# cont_board.net
KiCad netlist of a schematic drawn in Altium Designer
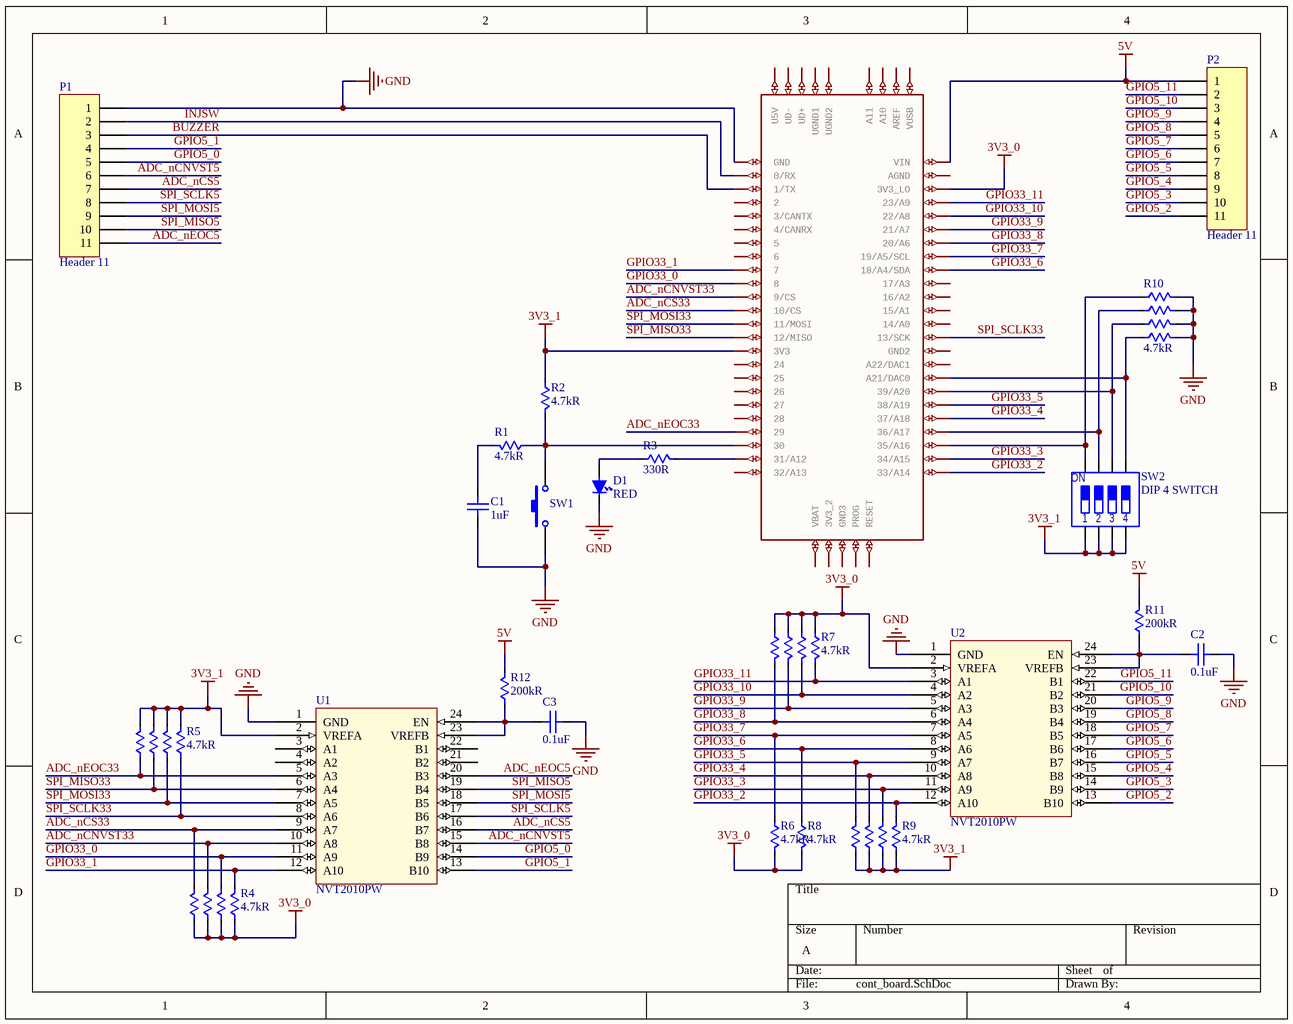
[diagram p0: cont_board.SchDoc]

(export (version "E")
  (design (tool "Eeschema 10.0.6"))
  (components
    (comp (ref "1")
      (value "TEENSY_3.5/3.6")
      (footprint "TEENSY_3.5/3.6")
      (libsource (lib "Schlib1") (part "TEENSY_3.5/3.6"))
    )
    (comp (ref "C1")
      (value "1uF")
      (footprint "CAP_0805")
      (description "Cap Ceramic 1uF 16V Y5V -20% to 80% Pad SMD 0805 85C T/R")
      (fields
        (field (name "MANUFACTURER") "KEMET")
        (field (name "MANUFACTURER PART NUMBER") "C0805C105Z4VACTU")
      )
      (libsource (lib "Schlib1") (part "C0805C105Z4VACTU"))
    )
    (comp (ref "C2")
      (value "0.1uF")
      (footprint "CAP_0805")
      (description "CAP CER 0.1UF 25V X7R 0805")
      (fields (field (name "MANUFACTURER") "KEMET") (field (name "TOLERANCE") "20%"))
      (libsource (lib "Schlib1") (part "C0805C104M3RACTU"))
    )
    (comp (ref "C3")
      (value "0.1uF")
      (footprint "CAP_0805")
      (description "CAP CER 0.1UF 25V X7R 0805")
      (fields (field (name "MANUFACTURER") "KEMET") (field (name "TOLERANCE") "20%"))
      (libsource (lib "Schlib1") (part "C0805C104M3RACTU"))
    )
    (comp (ref "D1")
      (value "RED")
      (footprint "150080SS75000")
      (description "WURTH ELEKTRONIK   150080SS75000   LED, 0805, SUP RED, 60MCD, 630NM")
      (fields
        (field (name "MANUFACTURER") "Wurth Electronics")
        (field (name "MANUFACTURER PART NUMBER") "150080SS75000")
      )
      (libsource (lib "Schlib1") (part "150080SS75000"))
    )
    (comp (ref "P1")
      (value "Header 11")
      (footprint "HDR1X11")
      (description "Header, 11-Pin")
      (fields (field (name "PUBLISHER") "Altium Limited"))
      (libsource (lib "Miscellaneous Connectors") (part "Header 11"))
    )
    (comp (ref "P2")
      (value "Header 11")
      (footprint "HDR1X11")
      (description "Header, 11-Pin")
      (fields (field (name "PUBLISHER") "Altium Limited"))
      (libsource (lib "") (part "Header 11_1"))
    )
    (comp (ref "R1")
      (value "4.7kR")
      (footprint "RES_0805_PANASONIC")
      (description "Res Thin Film 0805 4.7K Ohm 0.5% 0.125W(1/8W) ±25ppm/C Molded SMD Automotive Punched T/R")
      (fields
        (field (name "MANUFACTURER") "Panasonic")
        (field (name "MANUFACTURER PART NUMBER") "ERA-6AED472V")
      )
      (libsource (lib "Schlib1") (part "ERA-6AED472V"))
    )
    (comp (ref "R2")
      (value "4.7kR")
      (footprint "RES_0805_PANASONIC")
      (description "Res Thin Film 0805 4.7K Ohm 0.5% 0.125W(1/8W) ±25ppm/C Molded SMD Automotive Punched T/R")
      (fields
        (field (name "MANUFACTURER") "Panasonic")
        (field (name "MANUFACTURER PART NUMBER") "ERA-6AED472V")
      )
      (libsource (lib "Schlib1") (part "ERA-6AED472V"))
    )
    (comp (ref "R3")
      (value "330R")
      (footprint "RES_0805_PANASONIC")
      (description "Res Thin Film 0805 330 Ohm 0.5% 0.125W(1/8W) ±25ppm/C Molded SMD Automotive Punched T/R")
      (fields
        (field (name "MANUFACTURER") "Panasonic")
        (field (name "MANUFACTURER PART NUMBER") "ERA-6AED331V")
      )
      (libsource (lib "Schlib1") (part "ERA-6AED331V"))
    )
    (comp (ref "R4")
      (value "4.7kR")
      (footprint "CAY16-472J4LF")
      (description "RES ARRAY 4 RES 4.7K OHM 1206")
      (fields
        (field (name "MANUFACTURER") "Bourns")
        (field (name "MANUFACTURER PART NUMBER") "CAY16-472J4LF")
      )
      (libsource (lib "Schlib1") (part "CAY16-472J4LF"))
    )
    (comp (ref "R5")
      (value "4.7kR")
      (footprint "CAY16-472J4LF")
      (description "RES ARRAY 4 RES 4.7K OHM 1206")
      (fields
        (field (name "MANUFACTURER") "Bourns")
        (field (name "MANUFACTURER PART NUMBER") "CAY16-472J4LF")
      )
      (libsource (lib "Schlib1") (part "CAY16-472J4LF"))
    )
    (comp (ref "R6")
      (value "4.7kR")
      (footprint "RES_0805_PANASONIC")
      (description "Res Thin Film 0805 4.7K Ohm 0.5% 0.125W(1/8W) ±25ppm/C Molded SMD Automotive Punched T/R")
      (fields
        (field (name "MANUFACTURER") "Panasonic")
        (field (name "MANUFACTURER PART NUMBER") "ERA-6AED472V")
      )
      (libsource (lib "Schlib1") (part "ERA-6AED472V"))
    )
    (comp (ref "R7")
      (value "4.7kR")
      (footprint "CAY16-472J4LF")
      (description "RES ARRAY 4 RES 4.7K OHM 1206")
      (fields
        (field (name "MANUFACTURER") "Bourns")
        (field (name "MANUFACTURER PART NUMBER") "CAY16-472J4LF")
      )
      (libsource (lib "Schlib1") (part "CAY16-472J4LF"))
    )
    (comp (ref "R8")
      (value "4.7kR")
      (footprint "RES_0805_PANASONIC")
      (description "Res Thin Film 0805 4.7K Ohm 0.5% 0.125W(1/8W) ±25ppm/C Molded SMD Automotive Punched T/R")
      (fields
        (field (name "MANUFACTURER") "Panasonic")
        (field (name "MANUFACTURER PART NUMBER") "ERA-6AED472V")
      )
      (libsource (lib "Schlib1") (part "ERA-6AED472V"))
    )
    (comp (ref "R9")
      (value "4.7kR")
      (footprint "CAY16-472J4LF")
      (description "RES ARRAY 4 RES 4.7K OHM 1206")
      (fields
        (field (name "MANUFACTURER") "Bourns")
        (field (name "MANUFACTURER PART NUMBER") "CAY16-472J4LF")
      )
      (libsource (lib "Schlib1") (part "CAY16-472J4LF"))
    )
    (comp (ref "R10")
      (value "4.7kR")
      (footprint "CAY16-472J4LF")
      (description "RES ARRAY 4 RES 4.7K OHM 1206")
      (fields
        (field (name "MANUFACTURER") "Bourns")
        (field (name "MANUFACTURER PART NUMBER") "CAY16-472J4LF")
      )
      (libsource (lib "Schlib1") (part "CAY16-472J4LF"))
    )
    (comp (ref "R11")
      (value "200kR")
      (footprint "RES_0805_PANASONIC")
      (description "VISHAY         CRCW0805200KJNEA             RES, THICK FILM, 200K, 5%, 0.125W, 0805")
      (fields
        (field (name "MANUFACTURER") "Vishay Dale")
        (field (name "MANUFACTURER PART NUMBER") "CRCW0805200KJNEA")
      )
      (libsource (lib "Schlib1") (part "CRCW0805200KJNEA"))
    )
    (comp (ref "R12")
      (value "200kR")
      (footprint "RES_0805_PANASONIC")
      (description "VISHAY         CRCW0805200KJNEA             RES, THICK FILM, 200K, 5%, 0.125W, 0805")
      (fields
        (field (name "MANUFACTURER") "Vishay Dale")
        (field (name "MANUFACTURER PART NUMBER") "CRCW0805200KJNEA")
      )
      (libsource (lib "Schlib1") (part "CRCW0805200KJNEA"))
    )
    (comp (ref "SW1")
      (value "B3FS-1000P")
      (footprint "B3FS-1000P")
      (description "OMRON - B3FS1000P - SWITCH, FLAT, 6X6X3.1, 100GF")
      (fields (field (name "MANUFACTURER") "Omron"))
      (libsource (lib "Schlib1") (part "B3FS-1000P"))
    )
    (comp (ref "SW2")
      (value "DIP 4 SWITCH")
      (footprint "DS04-254-2-04BK-SMT-TR")
      (fields
        (field (name "MANUFACTURER") "CUI")
        (field (name "MANUFACTURER PART NUMBER") "DS04-254-2-04BK-SMT-TR")
      )
      (libsource (lib "Schlib1") (part "DS04-254-2-04BK-SMT-TR"))
    )
    (comp (ref "U1")
      (value "NVT2010PW")
      (footprint "NVT2010")
      (description "10 pin Bidirectional Level Shifter IC")
      (fields
        (field (name "MANUFACTURER") "NXP Semiconductors")
        (field (name "MANUFACTURER PART NUMBER") "NVT2010PW,118")
      )
      (libsource (lib "Schlib1") (part "NVT2010PW"))
    )
    (comp (ref "U2")
      (value "NVT2010PW")
      (footprint "NVT2010")
      (description "10 pin Bidirectional Level Shifter IC")
      (fields
        (field (name "MANUFACTURER") "NXP Semiconductors")
        (field (name "MANUFACTURER PART NUMBER") "NVT2010PW,118")
      )
      (libsource (lib "Schlib1") (part "NVT2010PW"))
    )
  )
  (nets
    (net (code "1") (name "/ADC_nCNVST5") (class "Default")
      (node (ref "P1") (pin "6") (pinfunction "6_6") (pintype "passive"))
      (node (ref "U1") (pin "15") (pinfunction "B8_15") (pintype "bidirectional"))
    )
    (net (code "2") (name "/ADC_nCNVST33") (class "Default")
      (node (ref "1") (pin "9/CS") (pinfunction "9/CS_9/CS") (pintype "bidirectional"))
      (node (ref "R4") (pin "6") (pinfunction "6_6") (pintype "passive"))
      (node (ref "U1") (pin "10") (pinfunction "A8_10") (pintype "bidirectional"))
    )
    (net (code "3") (name "/ADC_nCS5") (class "Default")
      (node (ref "P1") (pin "7") (pinfunction "7_7") (pintype "passive"))
      (node (ref "U1") (pin "16") (pinfunction "B7_16") (pintype "bidirectional"))
    )
    (net (code "4") (name "/ADC_nCS33") (class "Default")
      (node (ref "1") (pin "10/CS") (pinfunction "10/CS_10/CS") (pintype "bidirectional"))
      (node (ref "R4") (pin "8") (pinfunction "8_8") (pintype "passive"))
      (node (ref "U1") (pin "9") (pinfunction "A7_9") (pintype "bidirectional"))
    )
    (net (code "5") (name "/ADC_nEOC5") (class "Default")
      (node (ref "P1") (pin "11") (pinfunction "11_11") (pintype "passive"))
      (node (ref "U1") (pin "20") (pinfunction "B3_20") (pintype "bidirectional"))
    )
    (net (code "6") (name "/ADC_nEOC33") (class "Default")
      (node (ref "1") (pin "29") (pinfunction "29_29") (pintype "bidirectional"))
      (node (ref "R5") (pin "8") (pinfunction "8_8") (pintype "passive"))
      (node (ref "U1") (pin "5") (pinfunction "A3_5") (pintype "bidirectional"))
    )
    (net (code "7") (name "/BUZZER") (class "Default")
      (node (ref "1") (pin "1/TX") (pinfunction "1/TX_1/TX") (pintype "bidirectional"))
      (node (ref "P1") (pin "3") (pinfunction "3_3") (pintype "passive"))
    )
    (net (code "8") (name "/GPIO5_0") (class "Default")
      (node (ref "P1") (pin "5") (pinfunction "5_5") (pintype "passive"))
      (node (ref "U1") (pin "14") (pinfunction "B9_14") (pintype "bidirectional"))
    )
    (net (code "9") (name "/GPIO5_1") (class "Default")
      (node (ref "P1") (pin "4") (pinfunction "4_4") (pintype "passive"))
      (node (ref "U1") (pin "13") (pinfunction "B10_13") (pintype "bidirectional"))
    )
    (net (code "10") (name "/GPIO5_2") (class "Default")
      (node (ref "P2") (pin "11") (pinfunction "11_11") (pintype "passive"))
      (node (ref "U2") (pin "13") (pinfunction "B10_13") (pintype "bidirectional"))
    )
    (net (code "11") (name "/GPIO5_3") (class "Default")
      (node (ref "P2") (pin "10") (pinfunction "10_10") (pintype "passive"))
      (node (ref "U2") (pin "14") (pinfunction "B9_14") (pintype "bidirectional"))
    )
    (net (code "12") (name "/GPIO5_4") (class "Default")
      (node (ref "P2") (pin "9") (pinfunction "9_9") (pintype "passive"))
      (node (ref "U2") (pin "15") (pinfunction "B8_15") (pintype "bidirectional"))
    )
    (net (code "13") (name "/GPIO5_5") (class "Default")
      (node (ref "P2") (pin "8") (pinfunction "8_8") (pintype "passive"))
      (node (ref "U2") (pin "16") (pinfunction "B7_16") (pintype "bidirectional"))
    )
    (net (code "14") (name "/GPIO5_6") (class "Default")
      (node (ref "P2") (pin "7") (pinfunction "7_7") (pintype "passive"))
      (node (ref "U2") (pin "17") (pinfunction "B6_17") (pintype "bidirectional"))
    )
    (net (code "15") (name "/GPIO5_7") (class "Default")
      (node (ref "P2") (pin "6") (pinfunction "6_6") (pintype "passive"))
      (node (ref "U2") (pin "18") (pinfunction "B5_18") (pintype "bidirectional"))
    )
    (net (code "16") (name "/GPIO5_8") (class "Default")
      (node (ref "P2") (pin "5") (pinfunction "5_5") (pintype "passive"))
      (node (ref "U2") (pin "19") (pinfunction "B4_19") (pintype "bidirectional"))
    )
    (net (code "17") (name "/GPIO5_9") (class "Default")
      (node (ref "P2") (pin "4") (pinfunction "4_4") (pintype "passive"))
      (node (ref "U2") (pin "20") (pinfunction "B3_20") (pintype "bidirectional"))
    )
    (net (code "18") (name "/GPIO5_10") (class "Default")
      (node (ref "P2") (pin "3") (pinfunction "3_3") (pintype "passive"))
      (node (ref "U2") (pin "21") (pinfunction "B2_21") (pintype "bidirectional"))
    )
    (net (code "19") (name "/GPIO5_11") (class "Default")
      (node (ref "P2") (pin "2") (pinfunction "2_2") (pintype "passive"))
      (node (ref "U2") (pin "22") (pinfunction "B1_22") (pintype "bidirectional"))
    )
    (net (code "20") (name "/GPIO33_0") (class "Default")
      (node (ref "1") (pin "8") (pinfunction "8_8") (pintype "bidirectional"))
      (node (ref "R4") (pin "4") (pinfunction "4_4") (pintype "passive"))
      (node (ref "U1") (pin "11") (pinfunction "A9_11") (pintype "bidirectional"))
    )
    (net (code "21") (name "/GPIO33_1") (class "Default")
      (node (ref "1") (pin "7") (pinfunction "7_7") (pintype "bidirectional"))
      (node (ref "R4") (pin "2") (pinfunction "2_2") (pintype "passive"))
      (node (ref "U1") (pin "12") (pinfunction "A10_12") (pintype "bidirectional"))
    )
    (net (code "22") (name "/GPIO33_2") (class "Default")
      (node (ref "1") (pin "33/A14") (pinfunction "33/A14_33/A14") (pintype "bidirectional"))
      (node (ref "R9") (pin "2") (pinfunction "2_2") (pintype "passive"))
      (node (ref "U2") (pin "12") (pinfunction "A10_12") (pintype "bidirectional"))
    )
    (net (code "23") (name "/GPIO33_3") (class "Default")
      (node (ref "1") (pin "34/A15") (pinfunction "34/A15_34/A15") (pintype "bidirectional"))
      (node (ref "R9") (pin "4") (pinfunction "4_4") (pintype "passive"))
      (node (ref "U2") (pin "11") (pinfunction "A9_11") (pintype "bidirectional"))
    )
    (net (code "24") (name "/GPIO33_4") (class "Default")
      (node (ref "1") (pin "37/A18") (pinfunction "37/A18_37/A18") (pintype "bidirectional"))
      (node (ref "R9") (pin "6") (pinfunction "6_6") (pintype "passive"))
      (node (ref "U2") (pin "10") (pinfunction "A8_10") (pintype "bidirectional"))
    )
    (net (code "25") (name "/GPIO33_5") (class "Default")
      (node (ref "1") (pin "38/A19") (pinfunction "38/A19_38/A19") (pintype "bidirectional"))
      (node (ref "R9") (pin "8") (pinfunction "8_8") (pintype "passive"))
      (node (ref "U2") (pin "9") (pinfunction "A7_9") (pintype "bidirectional"))
    )
    (net (code "26") (name "/GPIO33_6") (class "Default")
      (node (ref "1") (pin "18/A4/SDA") (pinfunction "18/A4/SDA_18/A4/SDA") (pintype "bidirectional"))
      (node (ref "R8") (pin "1") (pinfunction "1_1") (pintype "passive"))
      (node (ref "U2") (pin "8") (pinfunction "A6_8") (pintype "bidirectional"))
    )
    (net (code "27") (name "/GPIO33_7") (class "Default")
      (node (ref "1") (pin "19/A5/SCL") (pinfunction "19/A5/SCL_19/A5/SCL") (pintype "bidirectional"))
      (node (ref "R6") (pin "1") (pinfunction "1_1") (pintype "passive"))
      (node (ref "U2") (pin "7") (pinfunction "A5_7") (pintype "bidirectional"))
    )
    (net (code "28") (name "/GPIO33_8") (class "Default")
      (node (ref "1") (pin "20/A6") (pinfunction "20/A6_20/A6") (pintype "bidirectional"))
      (node (ref "R7") (pin "2") (pinfunction "2_2") (pintype "passive"))
      (node (ref "U2") (pin "6") (pinfunction "A4_6") (pintype "bidirectional"))
    )
    (net (code "29") (name "/GPIO33_9") (class "Default")
      (node (ref "1") (pin "21/A7") (pinfunction "21/A7_21/A7") (pintype "bidirectional"))
      (node (ref "R7") (pin "4") (pinfunction "4_4") (pintype "passive"))
      (node (ref "U2") (pin "5") (pinfunction "A3_5") (pintype "bidirectional"))
    )
    (net (code "30") (name "/GPIO33_10") (class "Default")
      (node (ref "1") (pin "22/A8") (pinfunction "22/A8_22/A8") (pintype "bidirectional"))
      (node (ref "R7") (pin "6") (pinfunction "6_6") (pintype "passive"))
      (node (ref "U2") (pin "4") (pinfunction "A2_4") (pintype "bidirectional"))
    )
    (net (code "31") (name "/GPIO33_11") (class "Default")
      (node (ref "1") (pin "23/A9") (pinfunction "23/A9_23/A9") (pintype "bidirectional"))
      (node (ref "R7") (pin "8") (pinfunction "8_8") (pintype "passive"))
      (node (ref "U2") (pin "3") (pinfunction "A1_3") (pintype "bidirectional"))
    )
    (net (code "32") (name "/INJSW") (class "Default")
      (node (ref "1") (pin "0/RX") (pinfunction "0/RX_0/RX") (pintype "bidirectional"))
      (node (ref "P1") (pin "2") (pinfunction "2_2") (pintype "passive"))
    )
    (net (code "33") (name "/SPI_MISO5") (class "Default")
      (node (ref "P1") (pin "10") (pinfunction "10_10") (pintype "passive"))
      (node (ref "U1") (pin "19") (pinfunction "B4_19") (pintype "bidirectional"))
    )
    (net (code "34") (name "/SPI_MISO33") (class "Default")
      (node (ref "1") (pin "12/MISO") (pinfunction "12/MISO_12/MISO") (pintype "bidirectional"))
      (node (ref "R5") (pin "6") (pinfunction "6_6") (pintype "passive"))
      (node (ref "U1") (pin "6") (pinfunction "A4_6") (pintype "bidirectional"))
    )
    (net (code "35") (name "/SPI_MOSI5") (class "Default")
      (node (ref "P1") (pin "9") (pinfunction "9_9") (pintype "passive"))
      (node (ref "U1") (pin "18") (pinfunction "B5_18") (pintype "bidirectional"))
    )
    (net (code "36") (name "/SPI_MOSI33") (class "Default")
      (node (ref "1") (pin "11/MOSI") (pinfunction "11/MOSI_11/MOSI") (pintype "bidirectional"))
      (node (ref "R5") (pin "4") (pinfunction "4_4") (pintype "passive"))
      (node (ref "U1") (pin "7") (pinfunction "A5_7") (pintype "bidirectional"))
    )
    (net (code "37") (name "/SPI_SCLK5") (class "Default")
      (node (ref "P1") (pin "8") (pinfunction "8_8") (pintype "passive"))
      (node (ref "U1") (pin "17") (pinfunction "B6_17") (pintype "bidirectional"))
    )
    (net (code "38") (name "/SPI_SCLK33") (class "Default")
      (node (ref "1") (pin "13/SCK") (pinfunction "13/SCK_13/SCK") (pintype "bidirectional"))
      (node (ref "R5") (pin "2") (pinfunction "2_2") (pintype "passive"))
      (node (ref "U1") (pin "8") (pinfunction "A6_8") (pintype "bidirectional"))
    )
    (net (code "39") (name "3V3_0") (class "Default")
      (node (ref "1") (pin "3V3_LO") (pinfunction "3V3_LO_3V3_LO") (pintype "bidirectional"))
      (node (ref "R4") (pin "1") (pinfunction "1_1") (pintype "passive"))
      (node (ref "R4") (pin "3") (pinfunction "3_3") (pintype "passive"))
      (node (ref "R4") (pin "5") (pinfunction "5_5") (pintype "passive"))
      (node (ref "R4") (pin "7") (pinfunction "7_7") (pintype "passive"))
      (node (ref "R6") (pin "2") (pinfunction "2_2") (pintype "passive"))
      (node (ref "R7") (pin "1") (pinfunction "1_1") (pintype "passive"))
      (node (ref "R7") (pin "3") (pinfunction "3_3") (pintype "passive"))
      (node (ref "R7") (pin "5") (pinfunction "5_5") (pintype "passive"))
      (node (ref "R7") (pin "7") (pinfunction "7_7") (pintype "passive"))
      (node (ref "R8") (pin "2") (pinfunction "2_2") (pintype "passive"))
      (node (ref "U2") (pin "2") (pinfunction "VREFA_2") (pintype "input"))
    )
    (net (code "40") (name "3V3_1") (class "Default")
      (node (ref "1") (pin "3V3") (pinfunction "3V3_3V3") (pintype "bidirectional"))
      (node (ref "R2") (pin "1") (pinfunction "1_1") (pintype "passive"))
      (node (ref "R5") (pin "1") (pinfunction "1_1") (pintype "passive"))
      (node (ref "R5") (pin "3") (pinfunction "3_3") (pintype "passive"))
      (node (ref "R5") (pin "5") (pinfunction "5_5") (pintype "passive"))
      (node (ref "R5") (pin "7") (pinfunction "7_7") (pintype "passive"))
      (node (ref "R9") (pin "1") (pinfunction "1_1") (pintype "passive"))
      (node (ref "R9") (pin "3") (pinfunction "3_3") (pintype "passive"))
      (node (ref "R9") (pin "5") (pinfunction "5_5") (pintype "passive"))
      (node (ref "R9") (pin "7") (pinfunction "7_7") (pintype "passive"))
      (node (ref "SW2") (pin "5") (pinfunction "5_5") (pintype "passive"))
      (node (ref "SW2") (pin "6") (pinfunction "6_6") (pintype "passive"))
      (node (ref "SW2") (pin "7") (pinfunction "7_7") (pintype "passive"))
      (node (ref "SW2") (pin "8") (pinfunction "8_8") (pintype "passive"))
      (node (ref "U1") (pin "2") (pinfunction "VREFA_2") (pintype "input"))
    )
    (net (code "41") (name "5V") (class "Default")
      (node (ref "1") (pin "VIN") (pinfunction "VIN_VIN") (pintype "bidirectional"))
      (node (ref "P2") (pin "1") (pinfunction "1_1") (pintype "passive"))
      (node (ref "R11") (pin "2") (pinfunction "2_2") (pintype "passive"))
      (node (ref "R12") (pin "2") (pinfunction "2_2") (pintype "passive"))
    )
    (net (code "42") (name "GND") (class "Default")
      (node (ref "1") (pin "GND") (pinfunction "GND_GND") (pintype "bidirectional"))
      (node (ref "C1") (pin "1") (pinfunction "1_1") (pintype "passive"))
      (node (ref "C2") (pin "1") (pinfunction "1_1") (pintype "passive"))
      (node (ref "C3") (pin "1") (pinfunction "1_1") (pintype "passive"))
      (node (ref "D1") (pin "1") (pinfunction "1_1") (pintype "passive"))
      (node (ref "P1") (pin "1") (pinfunction "1_1") (pintype "passive"))
      (node (ref "R10") (pin "2") (pinfunction "2_2") (pintype "passive"))
      (node (ref "R10") (pin "4") (pinfunction "4_4") (pintype "passive"))
      (node (ref "R10") (pin "6") (pinfunction "6_6") (pintype "passive"))
      (node (ref "R10") (pin "8") (pinfunction "8_8") (pintype "passive"))
      (node (ref "SW1") (pin "1") (pinfunction "1_1") (pintype "passive"))
      (node (ref "U1") (pin "1") (pinfunction "GND_1") (pintype "power_in"))
      (node (ref "U2") (pin "1") (pinfunction "GND_1") (pintype "power_in"))
    )
    (net (code "43") (name "Net-(1-A21{slash}DAC0)") (class "Default")
      (node (ref "1") (pin "21/DAC0") (pinfunction "A21/DAC0_21/DAC0") (pintype "bidirectional"))
      (node (ref "R10") (pin "1") (pinfunction "1_1") (pintype "passive"))
      (node (ref "SW2") (pin "4") (pinfunction "4_4") (pintype "passive"))
    )
    (net (code "44") (name "Net-(1-Pad30)") (class "Default")
      (node (ref "1") (pin "30") (pinfunction "30_30") (pintype "bidirectional"))
      (node (ref "R1") (pin "1") (pinfunction "1_1") (pintype "passive"))
      (node (ref "R2") (pin "2") (pinfunction "2_2") (pintype "passive"))
      (node (ref "SW1") (pin "2") (pinfunction "2_2") (pintype "passive"))
    )
    (net (code "45") (name "Net-(1-Pad31{slash}A12)") (class "Default")
      (node (ref "1") (pin "31/A12") (pinfunction "31/A12_31/A12") (pintype "bidirectional"))
      (node (ref "R3") (pin "2") (pinfunction "2_2") (pintype "passive"))
    )
    (net (code "46") (name "Net-(1-Pad35{slash}A16)") (class "Default")
      (node (ref "1") (pin "35/A16") (pinfunction "35/A16_35/A16") (pintype "bidirectional"))
      (node (ref "R10") (pin "7") (pinfunction "7_7") (pintype "passive"))
      (node (ref "SW2") (pin "1") (pinfunction "1_1") (pintype "passive"))
    )
    (net (code "47") (name "Net-(1-Pad36{slash}A17)") (class "Default")
      (node (ref "1") (pin "36/A17") (pinfunction "36/A17_36/A17") (pintype "bidirectional"))
      (node (ref "R10") (pin "5") (pinfunction "5_5") (pintype "passive"))
      (node (ref "SW2") (pin "2") (pinfunction "2_2") (pintype "passive"))
    )
    (net (code "48") (name "Net-(1-Pad39{slash}A20)") (class "Default")
      (node (ref "1") (pin "39/A20") (pinfunction "39/A20_39/A20") (pintype "bidirectional"))
      (node (ref "R10") (pin "3") (pinfunction "3_3") (pintype "passive"))
      (node (ref "SW2") (pin "3") (pinfunction "3_3") (pintype "passive"))
    )
    (net (code "49") (name "Net-(C1-Pad2)") (class "Default")
      (node (ref "C1") (pin "2") (pinfunction "2_2") (pintype "passive"))
      (node (ref "R1") (pin "2") (pinfunction "2_2") (pintype "passive"))
    )
    (net (code "50") (name "Net-(D1-Pad2)") (class "Default")
      (node (ref "D1") (pin "2") (pinfunction "2_2") (pintype "passive"))
      (node (ref "R3") (pin "1") (pinfunction "1_1") (pintype "passive"))
    )
    (net (code "51") (name "Net-(U1-EN)") (class "Default")
      (node (ref "C3") (pin "2") (pinfunction "2_2") (pintype "passive"))
      (node (ref "R12") (pin "1") (pinfunction "1_1") (pintype "passive"))
      (node (ref "U1") (pin "23") (pinfunction "VREFB_23") (pintype "input"))
      (node (ref "U1") (pin "24") (pinfunction "EN_24") (pintype "input"))
    )
    (net (code "52") (name "Net-(U2-EN)") (class "Default")
      (node (ref "C2") (pin "2") (pinfunction "2_2") (pintype "passive"))
      (node (ref "R11") (pin "1") (pinfunction "1_1") (pintype "passive"))
      (node (ref "U2") (pin "23") (pinfunction "VREFB_23") (pintype "input"))
      (node (ref "U2") (pin "24") (pinfunction "EN_24") (pintype "input"))
    )
    (net (code "53") (name "unconnected-(1-Pad2)") (class "Default")
      (node (ref "1") (pin "2") (pinfunction "2_2") (pintype "bidirectional"))
    )
    (net (code "54") (name "unconnected-(1-Pad3V3_2)") (class "Default")
      (node (ref "1") (pin "3V3_2") (pinfunction "3V3_2_3V3_2") (pintype "bidirectional"))
    )
    (net (code "55") (name "unconnected-(1-Pad3{slash}CANTX)") (class "Default")
      (node (ref "1") (pin "3/CANTX") (pinfunction "3/CANTX_3/CANTX") (pintype "bidirectional"))
    )
    (net (code "56") (name "unconnected-(1-Pad4{slash}CANRX)") (class "Default")
      (node (ref "1") (pin "4/CANRX") (pinfunction "4/CANRX_4/CANRX") (pintype "bidirectional"))
    )
    (net (code "57") (name "unconnected-(1-Pad5)") (class "Default")
      (node (ref "1") (pin "5") (pinfunction "5_5") (pintype "bidirectional"))
    )
    (net (code "58") (name "unconnected-(1-Pad6)") (class "Default")
      (node (ref "1") (pin "6") (pinfunction "6_6") (pintype "bidirectional"))
    )
    (net (code "59") (name "unconnected-(1-Pad14{slash}A0)") (class "Default")
      (node (ref "1") (pin "14/A0") (pinfunction "14/A0_14/A0") (pintype "bidirectional"))
    )
    (net (code "60") (name "unconnected-(1-Pad15{slash}A1)") (class "Default")
      (node (ref "1") (pin "15/A1") (pinfunction "15/A1_15/A1") (pintype "bidirectional"))
    )
    (net (code "61") (name "unconnected-(1-Pad16{slash}A2)") (class "Default")
      (node (ref "1") (pin "16/A2") (pinfunction "16/A2_16/A2") (pintype "bidirectional"))
    )
    (net (code "62") (name "unconnected-(1-Pad17{slash}A3)") (class "Default")
      (node (ref "1") (pin "17/A3") (pinfunction "17/A3_17/A3") (pintype "bidirectional"))
    )
    (net (code "63") (name "unconnected-(1-Pad24)") (class "Default")
      (node (ref "1") (pin "24") (pinfunction "24_24") (pintype "bidirectional"))
    )
    (net (code "64") (name "unconnected-(1-Pad25)") (class "Default")
      (node (ref "1") (pin "25") (pinfunction "25_25") (pintype "bidirectional"))
    )
    (net (code "65") (name "unconnected-(1-Pad26)") (class "Default")
      (node (ref "1") (pin "26") (pinfunction "26_26") (pintype "bidirectional"))
    )
    (net (code "66") (name "unconnected-(1-Pad27)") (class "Default")
      (node (ref "1") (pin "27") (pinfunction "27_27") (pintype "bidirectional"))
    )
    (net (code "67") (name "unconnected-(1-Pad28)") (class "Default")
      (node (ref "1") (pin "28") (pinfunction "28_28") (pintype "bidirectional"))
    )
    (net (code "68") (name "unconnected-(1-Pad32{slash}A13)") (class "Default")
      (node (ref "1") (pin "32/A13") (pinfunction "32/A13_32/A13") (pintype "bidirectional"))
    )
    (net (code "69") (name "unconnected-(1-PadA10)") (class "Default")
      (node (ref "1") (pin "A10") (pinfunction "A10_A10") (pintype "bidirectional"))
    )
    (net (code "70") (name "unconnected-(1-PadA11)") (class "Default")
      (node (ref "1") (pin "A11") (pinfunction "A11_A11") (pintype "bidirectional"))
    )
    (net (code "71") (name "unconnected-(1-PadA22{slash}DAC1)") (class "Default")
      (node (ref "1") (pin "A22/DAC1") (pinfunction "A22/DAC1_A22/DAC1") (pintype "bidirectional"))
    )
    (net (code "72") (name "unconnected-(1-PadAGND)") (class "Default")
      (node (ref "1") (pin "AGND") (pinfunction "AGND_AGND") (pintype "bidirectional"))
    )
    (net (code "73") (name "unconnected-(1-PadAREF)") (class "Default")
      (node (ref "1") (pin "AREF") (pinfunction "AREF_AREF") (pintype "bidirectional"))
    )
    (net (code "74") (name "unconnected-(1-PadGND2)") (class "Default")
      (node (ref "1") (pin "GND2") (pinfunction "GND2_GND2") (pintype "bidirectional"))
    )
    (net (code "75") (name "unconnected-(1-PadGND3)") (class "Default")
      (node (ref "1") (pin "GND3") (pinfunction "GND3_GND3") (pintype "bidirectional"))
    )
    (net (code "76") (name "unconnected-(1-PadPROG)") (class "Default")
      (node (ref "1") (pin "PROG") (pinfunction "PROG_PROG") (pintype "bidirectional"))
    )
    (net (code "77") (name "unconnected-(1-PadRESET)") (class "Default")
      (node (ref "1") (pin "RESET") (pinfunction "RESET_RESET") (pintype "bidirectional"))
    )
    (net (code "78") (name "unconnected-(1-PadU5V)") (class "Default")
      (node (ref "1") (pin "U5V") (pinfunction "U5V_U5V") (pintype "bidirectional"))
    )
    (net (code "79") (name "unconnected-(1-PadUD+)") (class "Default")
      (node (ref "1") (pin "UD+") (pinfunction "UD+_UD+") (pintype "bidirectional"))
    )
    (net (code "80") (name "unconnected-(1-PadUD-)") (class "Default")
      (node (ref "1") (pin "UD-") (pinfunction "UD-_UD-") (pintype "bidirectional"))
    )
    (net (code "81") (name "unconnected-(1-PadUGND1)") (class "Default")
      (node (ref "1") (pin "UGND1") (pinfunction "UGND1_UGND1") (pintype "bidirectional"))
    )
    (net (code "82") (name "unconnected-(1-PadUGND2)") (class "Default")
      (node (ref "1") (pin "UGND2") (pinfunction "UGND2_UGND2") (pintype "bidirectional"))
    )
    (net (code "83") (name "unconnected-(1-PadVBAT)") (class "Default")
      (node (ref "1") (pin "VBAT") (pinfunction "VBAT_VBAT") (pintype "bidirectional"))
    )
    (net (code "84") (name "unconnected-(1-PadVUSB)") (class "Default")
      (node (ref "1") (pin "VUSB") (pinfunction "VUSB_VUSB") (pintype "bidirectional"))
    )
    (net (code "85") (name "unconnected-(U1-A1-Pad3)") (class "Default")
      (node (ref "U1") (pin "3") (pinfunction "A1_3") (pintype "bidirectional"))
    )
    (net (code "86") (name "unconnected-(U1-A2-Pad4)") (class "Default")
      (node (ref "U1") (pin "4") (pinfunction "A2_4") (pintype "bidirectional"))
    )
    (net (code "87") (name "unconnected-(U1-B1-Pad22)") (class "Default")
      (node (ref "U1") (pin "22") (pinfunction "B1_22") (pintype "bidirectional"))
    )
    (net (code "88") (name "unconnected-(U1-B2-Pad21)") (class "Default")
      (node (ref "U1") (pin "21") (pinfunction "B2_21") (pintype "bidirectional"))
    )
  )
)
